# ble_bme690_node.net
KiCad netlist of a schematic drawn in EAGLE
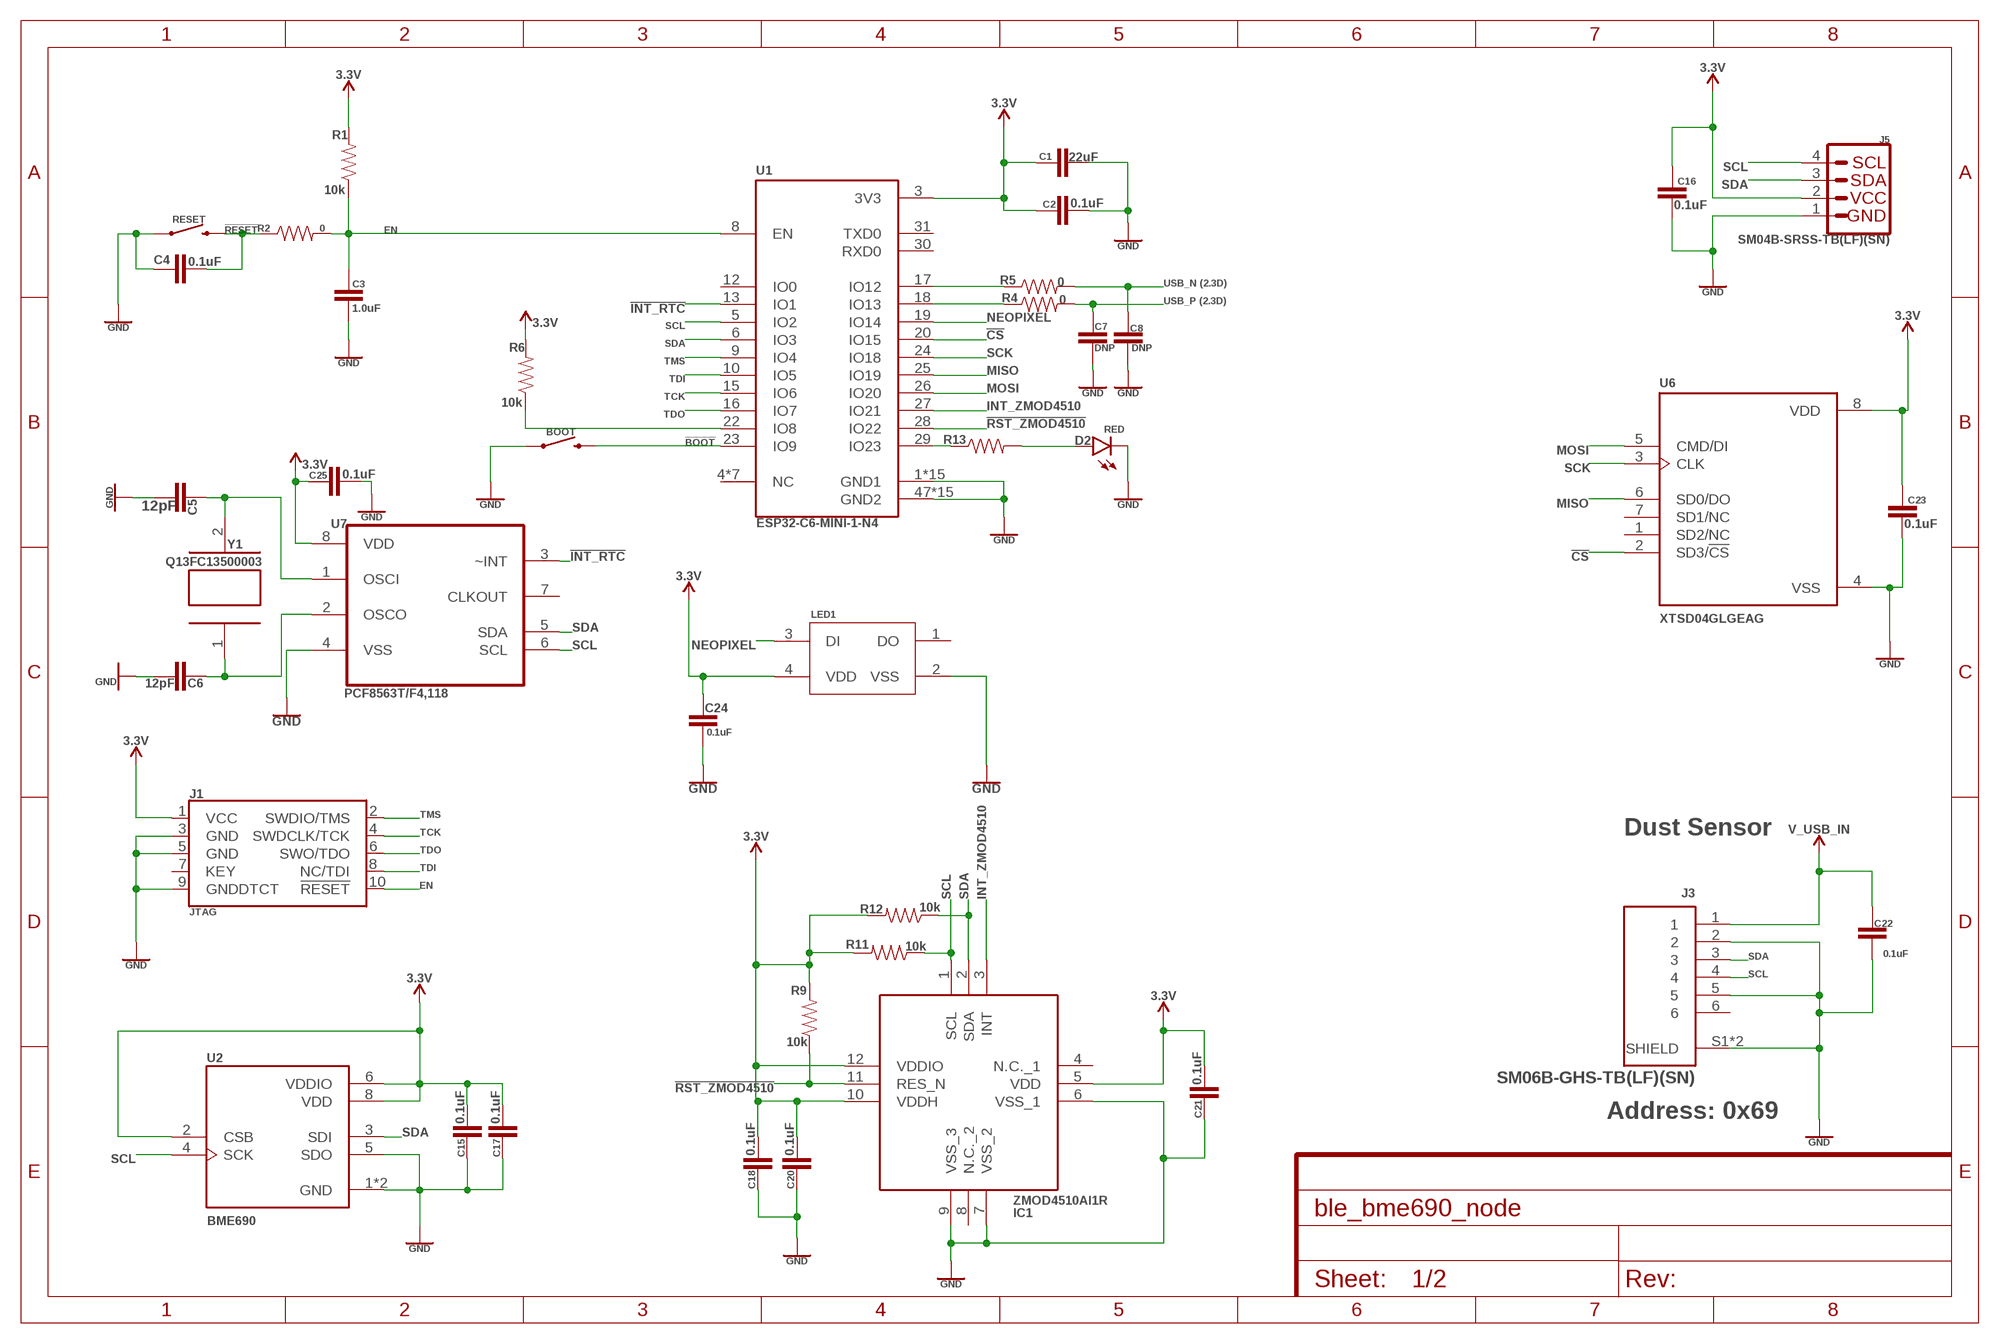
[diagram p0: schematic, sheet 1]
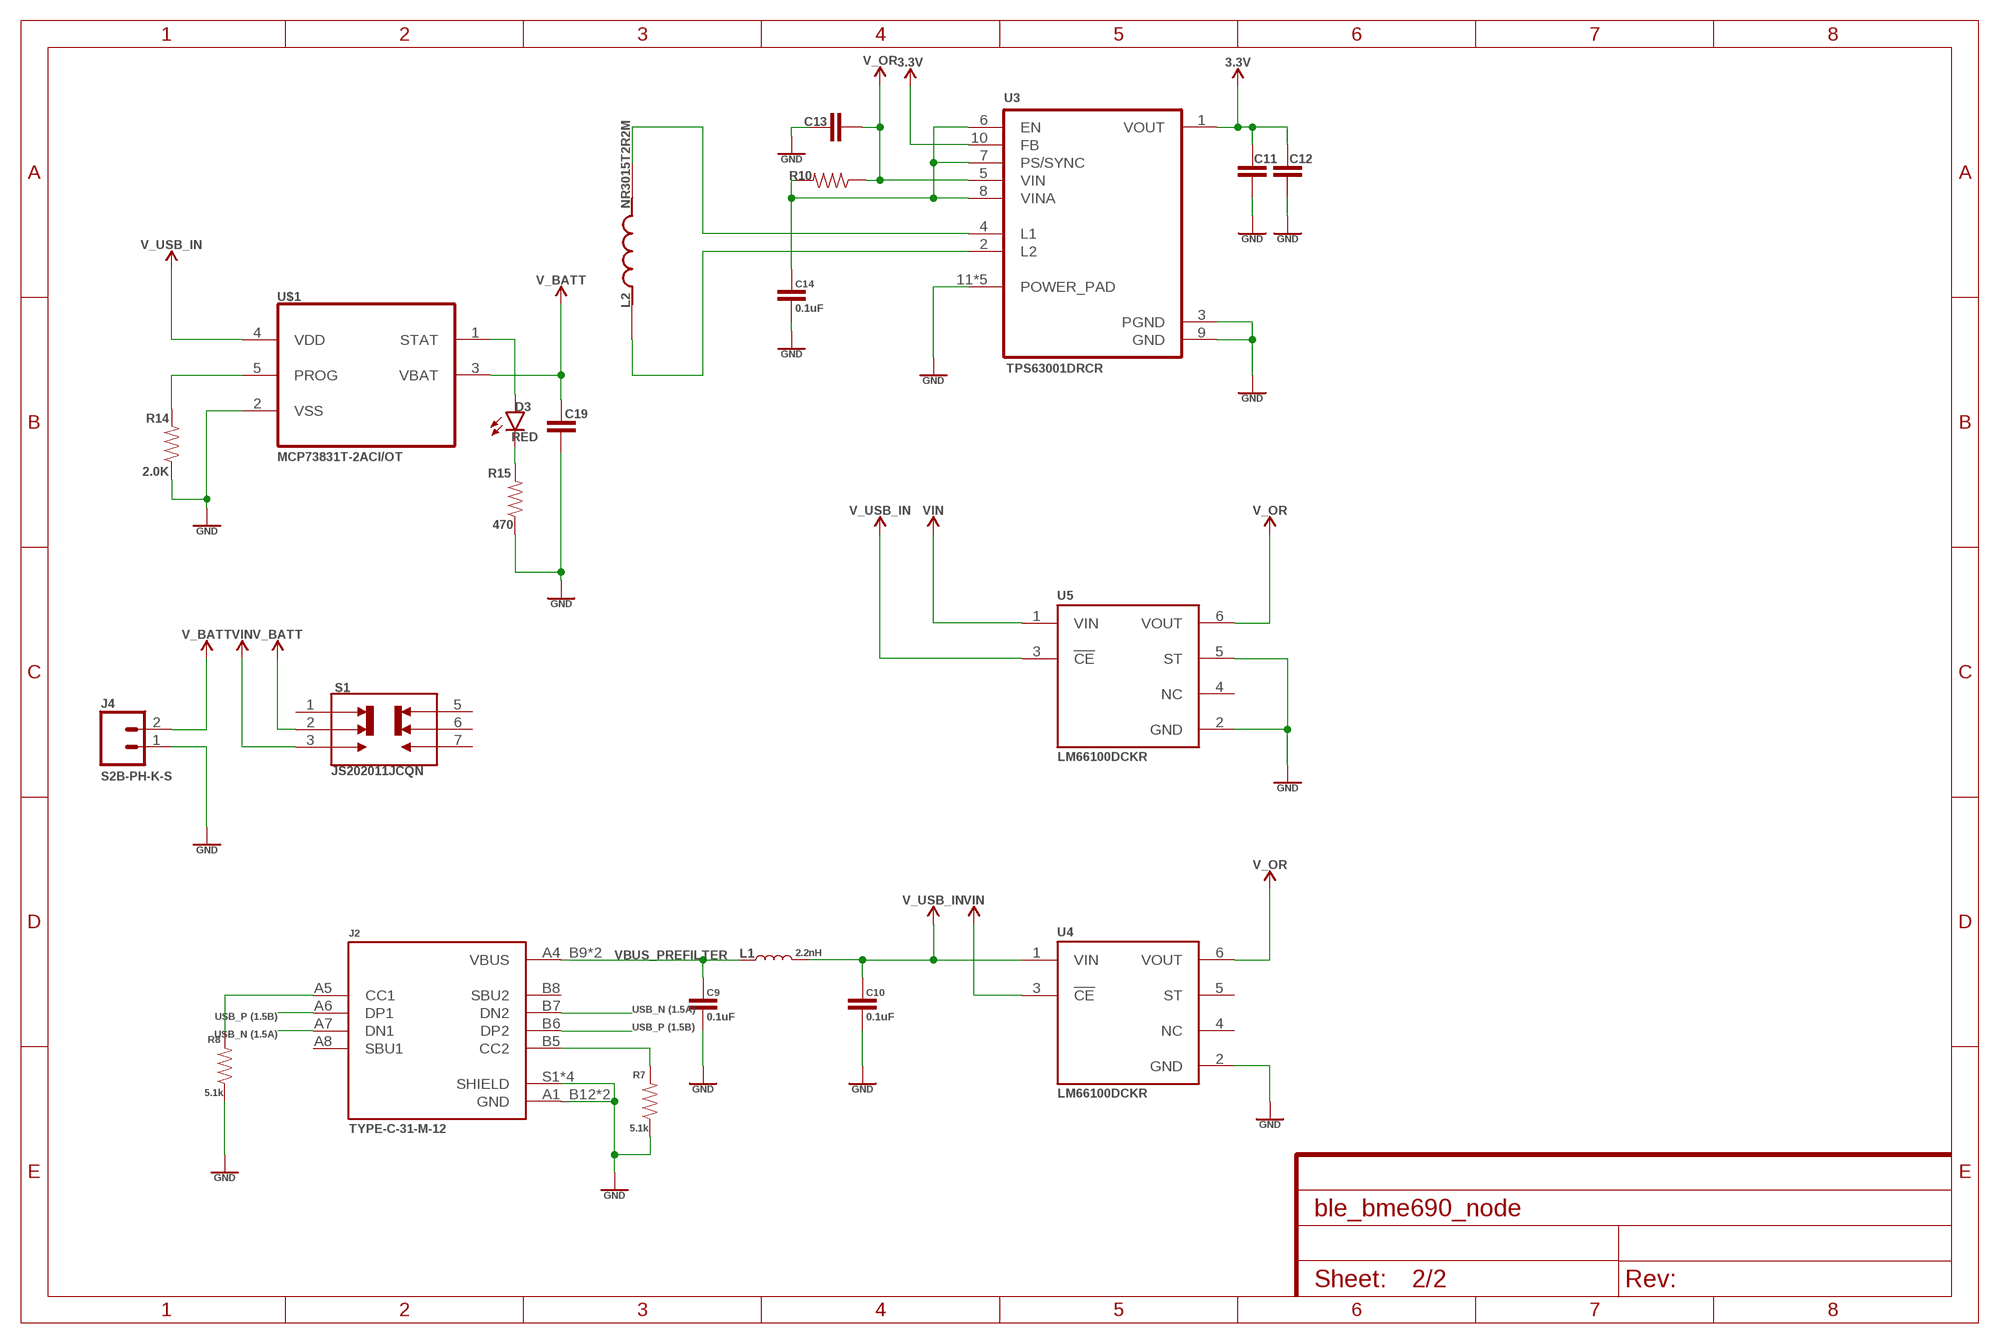
[diagram p1: schematic, sheet 2]

(export (version "E")
  (design (tool "Eeschema 10.0.6"))
  (components
    (comp (ref "BOOT")
      (value "MOMENTARY-SWITCH-SPST-SMD-4.6X2.8MM")
      (footprint "eagle-import:TACTILE_SWITCH_SMD_4.6X2.8MM")
      (libsource (lib "eagle-import") (part "MOMENTARY-SWITCH-SPST-SMD-4.6X2.8MM"))
    )
    (comp (ref "C1")
      (value "22uF")
      (footprint "eagle-import:0603")
      (libsource (lib "eagle-import") (part "22UF-0603-6.3V-20%"))
    )
    (comp (ref "C2")
      (value "0.1uF")
      (footprint "eagle-import:0402")
      (libsource (lib "eagle-import") (part "SparkFun-Capacitors_Sai_0.1UF-0402-6.3V-10%-X7R"))
    )
    (comp (ref "C3")
      (value "1.0uF")
      (footprint "eagle-import:0402")
      (libsource (lib "eagle-import") (part "1.0UF-0402-16V-10%"))
    )
    (comp (ref "C4")
      (value "0.1uF")
      (footprint "eagle-import:0402")
      (libsource (lib "eagle-import") (part "SparkFun-Capacitors_Sai_0.1UF-0402-6.3V-10%-X7R"))
    )
    (comp (ref "C5")
      (value "12pF")
      (footprint "eagle-import:0402")
      (libsource (lib "eagle-import") (part "12PF-0402-50V-5%"))
    )
    (comp (ref "C6")
      (value "12pF")
      (footprint "eagle-import:0402")
      (libsource (lib "eagle-import") (part "12PF-0402-50V-5%"))
    )
    (comp (ref "C7")
      (value "DNP")
      (footprint "eagle-import:0402")
      (libsource (lib "eagle-import") (part "0.1UF-0402-6.3V-10%-X7R"))
    )
    (comp (ref "C8")
      (value "DNP")
      (footprint "eagle-import:0402")
      (libsource (lib "eagle-import") (part "0.1UF-0402-6.3V-10%-X7R"))
    )
    (comp (ref "C15")
      (value "0.1uF")
      (footprint "eagle-import:0402")
      (libsource (lib "eagle-import") (part "SparkFun-Capacitors_Sai_0.1UF-0402-6.3V-10%-X7R"))
    )
    (comp (ref "C16")
      (value "0.1uF")
      (footprint "eagle-import:0402")
      (libsource (lib "eagle-import") (part "SparkFun-Capacitors_Sai_0.1UF-0402-6.3V-10%-X7R"))
    )
    (comp (ref "C17")
      (value "0.1uF")
      (footprint "eagle-import:0402")
      (libsource (lib "eagle-import") (part "SparkFun-Capacitors_Sai_0.1UF-0402-6.3V-10%-X7R"))
    )
    (comp (ref "C18")
      (value "0.1uF")
      (footprint "eagle-import:0402")
      (libsource (lib "eagle-import") (part "SparkFun-Capacitors_Sai_0.1UF-0402-6.3V-10%-X7R"))
    )
    (comp (ref "C20")
      (value "0.1uF")
      (footprint "eagle-import:0402")
      (libsource (lib "eagle-import") (part "SparkFun-Capacitors_Sai_0.1UF-0402-6.3V-10%-X7R"))
    )
    (comp (ref "C21")
      (value "0.1uF")
      (footprint "eagle-import:0402")
      (libsource (lib "eagle-import") (part "SparkFun-Capacitors_Sai_0.1UF-0402-6.3V-10%-X7R"))
    )
    (comp (ref "C22")
      (value "0.1uF")
      (footprint "eagle-import:0402")
      (libsource (lib "eagle-import") (part "0.1UF-0402-16V-10%"))
    )
    (comp (ref "C23")
      (value "0.1uF")
      (footprint "eagle-import:0402")
      (libsource (lib "eagle-import") (part "SparkFun-Capacitors_Sai_0.1UF-0402-6.3V-10%-X7R"))
    )
    (comp (ref "C24")
      (value "0.1uF")
      (footprint "eagle-import:0402")
      (libsource (lib "eagle-import") (part "0.1UF-0402-16V-10%"))
    )
    (comp (ref "C25")
      (value "0.1uF")
      (footprint "eagle-import:0402")
      (libsource (lib "eagle-import") (part "SparkFun-Capacitors_Sai_0.1UF-0402-6.3V-10%-X7R"))
    )
    (comp (ref "D2")
      (value "RED")
      (footprint "eagle-import:LED-0603")
      (libsource (lib "eagle-import") (part "LED-RED0603"))
    )
    (comp (ref "IC1")
      (value "ZMOD4510AI1R")
      (footprint "eagle-import:ZMOD4510AI1R")
      (fields (field (name "MOUSER_PART_NUMBER") "972-ZMOD4510AI1R"))
      (libsource (lib "eagle-import") (part "ZMOD4510AI1R"))
    )
    (comp (ref "J1")
      (value "JTAG")
      (footprint "eagle-import:2X5-SMD-UNSHROUDED")
      (libsource (lib "eagle-import") (part "CORTEX_JTAG_DEBUG_SMD-UNSHROUDED"))
    )
    (comp (ref "J3")
      (value "SM06B-GHS-TB(LF)(SN)")
      (footprint "eagle-import:JST_SM06B-GHS-TB(LF)(SN)")
      (fields (field (name "MF") "JST Sales America Inc."))
      (libsource (lib "eagle-import") (part "SM06B-GHS-TB(LF)(SN)"))
    )
    (comp (ref "J5")
      (value "SM04B-SRSS-TB(LF)(SN)")
      (footprint "eagle-import:1X04_1MM_RA")
      (libsource (lib "eagle-import") (part "QWIIC_CONNECTORJS-1MM"))
    )
    (comp (ref "LED1")
      (value "WS2812B-2020")
      (footprint "eagle-import:WS2812B-2020")
      (fields (field (name "MF") "WorldSemi"))
      (libsource (lib "eagle-import") (part "WS2812B-2020"))
    )
    (comp (ref "R1")
      (value "10k")
      (footprint "eagle-import:0402")
      (libsource (lib "eagle-import") (part "10KOHM-0402-1/16W-1%"))
    )
    (comp (ref "R2")
      (value "0")
      (footprint "eagle-import:0402")
      (libsource (lib "eagle-import") (part "0OHM-0402-1/10W"))
    )
    (comp (ref "R4")
      (value "0")
      (footprint "eagle-import:0402")
      (libsource (lib "eagle-import") (part "0OHM-0402-1/10W"))
    )
    (comp (ref "R5")
      (value "0")
      (footprint "eagle-import:0402")
      (libsource (lib "eagle-import") (part "0OHM-0402-1/10W"))
    )
    (comp (ref "R6")
      (value "10k")
      (footprint "eagle-import:0402")
      (libsource (lib "eagle-import") (part "10KOHM-0402-1/16W-1%"))
    )
    (comp (ref "R9")
      (value "10k")
      (footprint "eagle-import:0402")
      (libsource (lib "eagle-import") (part "10KOHM-0402-1/16W-1%"))
    )
    (comp (ref "R11")
      (value "10k")
      (footprint "eagle-import:0402")
      (libsource (lib "eagle-import") (part "10KOHM-0402-1/16W-1%"))
    )
    (comp (ref "R12")
      (value "10k")
      (footprint "eagle-import:0402")
      (libsource (lib "eagle-import") (part "10KOHM-0402-1/16W-1%"))
    )
    (comp (ref "R13")
      (value "100OHM")
      (footprint "eagle-import:0402")
      (libsource (lib "eagle-import") (part "100OHM"))
    )
    (comp (ref "RESET")
      (value "MOMENTARY-SWITCH-SPST-SMD-4.6X2.8MM")
      (footprint "eagle-import:TACTILE_SWITCH_SMD_4.6X2.8MM")
      (libsource (lib "eagle-import") (part "MOMENTARY-SWITCH-SPST-SMD-4.6X2.8MM"))
    )
    (comp (ref "U1")
      (value "ESP32-C6-MINI-1-N4")
      (footprint "eagle-import:XCVR_ESP32-C6-MINI-1-N4")
      (fields (field (name "MF") "Espressif Systems"))
      (libsource (lib "eagle-import") (part "ESP32-C6-MINI-1-N4"))
    )
    (comp (ref "U2")
      (value "BME690")
      (footprint "eagle-import:IC_BME688")
      (fields (field (name "MF") "Bosch Sensortec") (field (name "MP") "BME688"))
      (libsource (lib "eagle-import") (part "BME690"))
    )
    (comp (ref "U6")
      (value "XTSD04GLGEAG")
      (footprint "eagle-import:SON127P600X800X95-8N")
      (fields (field (name "MF") "XTX"))
      (libsource (lib "eagle-import") (part "XTSD04GLGEAG"))
    )
    (comp (ref "U7")
      (value "PCF8563T/F4,118")
      (footprint "eagle-import:SOIC127P600X175-8N")
      (fields (field (name "MF") "NXP USA"))
      (libsource (lib "eagle-import") (part "PCF8563T/F4,118"))
    )
    (comp (ref "Y1")
      (value "Q13FC13500003")
      (footprint "eagle-import:XTAL_FC-135_32.7680KA-A0")
      (fields (field (name "MF") "EPSON") (field (name "MP") "FC-135 32.7680KA-A0"))
      (libsource (lib "eagle-import") (part "FC-135_32.7680KA-A0"))
    )
    (comp (ref "C9")
      (value "0.1uF")
      (footprint "eagle-import:0402")
      (libsource (lib "eagle-import") (part "SparkFun-Capacitors_Sai_0.1UF-0402-6.3V-10%-X7R"))
    )
    (comp (ref "C10")
      (value "0.1uF")
      (footprint "eagle-import:0402")
      (libsource (lib "eagle-import") (part "SparkFun-Capacitors_Sai_0.1UF-0402-6.3V-10%-X7R"))
    )
    (comp (ref "C11")
      (value "10UF0402")
      (footprint "eagle-import:0402")
      (libsource (lib "eagle-import") (part "10UF0402"))
    )
    (comp (ref "C12")
      (value "10UF0402")
      (footprint "eagle-import:0402")
      (libsource (lib "eagle-import") (part "10UF0402"))
    )
    (comp (ref "C13")
      (value "10UF0402")
      (footprint "eagle-import:0402")
      (libsource (lib "eagle-import") (part "10UF0402"))
    )
    (comp (ref "C14")
      (value "0.1uF")
      (footprint "eagle-import:0402")
      (libsource (lib "eagle-import") (part "SparkFun-Capacitors_Sai_0.1UF-0402-6.3V-10%-X7R"))
    )
    (comp (ref "C19")
      (value "4.7UF0402")
      (footprint "eagle-import:0402")
      (libsource (lib "eagle-import") (part "4.7UF0402"))
    )
    (comp (ref "D3")
      (value "RED")
      (footprint "eagle-import:LED-0603")
      (libsource (lib "eagle-import") (part "LED-RED0603"))
    )
    (comp (ref "J2")
      (value "TYPE-C-31-M-12")
      (footprint "eagle-import:HRO_TYPE-C-31-M-12")
      (fields (field (name "MF") "HRO Electronics Co., Ltd."))
      (libsource (lib "eagle-import") (part "TYPE-C-31-M-12"))
    )
    (comp (ref "J4")
      (value "S2B-PH-K-S")
      (footprint "eagle-import:JST-2-PTH-NS")
      (libsource (lib "eagle-import") (part "CONN_02-JST-2-PTH-NO_SILK"))
    )
    (comp (ref "L1")
      (value "2.2nH")
      (footprint "eagle-import:0603")
      (libsource (lib "eagle-import") (part "3.9NH"))
    )
    (comp (ref "L2")
      (value "NR3015T2R2M")
      (footprint "eagle-import:IND_NR3015T2R2M")
      (fields (field (name "MF") "Taiyo Yuden"))
      (libsource (lib "eagle-import") (part "NR3015T2R2M"))
    )
    (comp (ref "R7")
      (value "5.1k")
      (footprint "eagle-import:0402")
      (libsource (lib "eagle-import") (part "5.1KOHM-0402-1/16W-1%"))
    )
    (comp (ref "R8")
      (value "5.1k")
      (footprint "eagle-import:0402")
      (libsource (lib "eagle-import") (part "5.1KOHM-0402-1/16W-1%"))
    )
    (comp (ref "R10")
      (value "100OHM")
      (footprint "eagle-import:0402")
      (libsource (lib "eagle-import") (part "100OHM"))
    )
    (comp (ref "R14")
      (value "2.0K")
      (footprint "eagle-import:0402")
      (libsource (lib "eagle-import") (part "2.0KOHM-0402-1/16W-1%"))
    )
    (comp (ref "R15")
      (value "470")
      (footprint "eagle-import:0402")
      (libsource (lib "eagle-import") (part "470OHM-0402-1/16W-5%"))
    )
    (comp (ref "S1")
      (value "JS202011JCQN")
      (footprint "eagle-import:SW_JS202011JCQN")
      (fields (field (name "MF") "C&K"))
      (libsource (lib "eagle-import") (part "JS202011JCQN"))
    )
    (comp (ref "U$1")
      (value "MCP73831T-2ACI/OT")
      (footprint "eagle-import:SOT95P280X145-5N")
      (fields (field (name "MF") "Microchip"))
      (libsource (lib "eagle-import") (part "MCP73831T-2ACI/OT"))
    )
    (comp (ref "U3")
      (value "TPS63001DRCR")
      (footprint "eagle-import:VREG_V62_16624-01YE")
      (fields (field (name "MF") "Texas Instruments"))
      (libsource (lib "eagle-import") (part "TPS63001DRCR"))
    )
    (comp (ref "U4")
      (value "LM66100DCKR")
      (footprint "eagle-import:SOT65P210X110-6N")
      (fields (field (name "MF") "Texas Instruments"))
      (libsource (lib "eagle-import") (part "LM66100DCKR"))
    )
    (comp (ref "U5")
      (value "LM66100DCKR")
      (footprint "eagle-import:SOT65P210X110-6N")
      (fields (field (name "MF") "Texas Instruments"))
      (libsource (lib "eagle-import") (part "LM66100DCKR"))
    )
  )
  (nets
    (net (code "1") (name "3.3V") (class "Default")
      (node (ref "C1") (pin "1") (pinfunction "1_1") (pintype "passive"))
      (node (ref "C11") (pin "1") (pinfunction "1_1") (pintype "passive"))
      (node (ref "C12") (pin "1") (pinfunction "1_1") (pintype "passive"))
      (node (ref "C15") (pin "2") (pinfunction "2_2") (pintype "passive"))
      (node (ref "C16") (pin "2") (pinfunction "2_2") (pintype "passive"))
      (node (ref "C17") (pin "2") (pinfunction "2_2") (pintype "passive"))
      (node (ref "C18") (pin "2") (pinfunction "2_2") (pintype "passive"))
      (node (ref "C2") (pin "1") (pinfunction "1_1") (pintype "passive"))
      (node (ref "C20") (pin "2") (pinfunction "2_2") (pintype "passive"))
      (node (ref "C21") (pin "2") (pinfunction "2_2") (pintype "passive"))
      (node (ref "C23") (pin "2") (pinfunction "2_2") (pintype "passive"))
      (node (ref "C24") (pin "1") (pinfunction "1_1") (pintype "passive"))
      (node (ref "C25") (pin "1") (pinfunction "1_1") (pintype "passive"))
      (node (ref "IC1") (pin "10") (pinfunction "VDDH_10") (pintype "bidirectional"))
      (node (ref "IC1") (pin "12") (pinfunction "VDDIO_12") (pintype "bidirectional"))
      (node (ref "IC1") (pin "5") (pinfunction "VDD_5") (pintype "bidirectional"))
      (node (ref "J1") (pin "1") (pinfunction "VCC_1") (pintype "bidirectional"))
      (node (ref "J5") (pin "2") (pinfunction "2_2") (pintype "power_in"))
      (node (ref "LED1") (pin "4") (pinfunction "VDD_4") (pintype "bidirectional"))
      (node (ref "R1") (pin "2") (pinfunction "2_2") (pintype "passive"))
      (node (ref "R11") (pin "2") (pinfunction "2_2") (pintype "passive"))
      (node (ref "R12") (pin "2") (pinfunction "2_2") (pintype "passive"))
      (node (ref "R6") (pin "2") (pinfunction "2_2") (pintype "passive"))
      (node (ref "R9") (pin "2") (pinfunction "2_2") (pintype "passive"))
      (node (ref "U1") (pin "3") (pinfunction "3V3_3") (pintype "power_in"))
      (node (ref "U2") (pin "2") (pinfunction "CSB_2") (pintype "input"))
      (node (ref "U2") (pin "6") (pinfunction "VDDIO_6") (pintype "power_in"))
      (node (ref "U2") (pin "8") (pinfunction "VDD_8") (pintype "power_in"))
      (node (ref "U3") (pin "1") (pinfunction "VOUT_1") (pintype "output"))
      (node (ref "U3") (pin "10") (pinfunction "FB_10") (pintype "input"))
      (node (ref "U6") (pin "8") (pinfunction "VDD_8") (pintype "power_in"))
      (node (ref "U7") (pin "8") (pinfunction "VDD_8") (pintype "power_in"))
    )
    (net (code "2") (name "EN") (class "Default")
      (node (ref "C3") (pin "2") (pinfunction "2_2") (pintype "passive"))
      (node (ref "J1") (pin "10") (pinfunction "~{RESET}_10") (pintype "bidirectional"))
      (node (ref "R1") (pin "1") (pinfunction "1_1") (pintype "passive"))
      (node (ref "R2") (pin "2") (pinfunction "2_2") (pintype "passive"))
      (node (ref "U1") (pin "8") (pinfunction "EN_8") (pintype "input"))
    )
    (net (code "3") (name "GND") (class "Default")
      (node (ref "BOOT") (pin "1") (pinfunction "1_1") (pintype "passive"))
      (node (ref "BOOT") (pin "2") (pinfunction "1_2") (pintype "passive"))
      (node (ref "C1") (pin "2") (pinfunction "2_2") (pintype "passive"))
      (node (ref "C10") (pin "1") (pinfunction "1_1") (pintype "passive"))
      (node (ref "C11") (pin "2") (pinfunction "2_2") (pintype "passive"))
      (node (ref "C12") (pin "2") (pinfunction "2_2") (pintype "passive"))
      (node (ref "C13") (pin "1") (pinfunction "1_1") (pintype "passive"))
      (node (ref "C14") (pin "1") (pinfunction "1_1") (pintype "passive"))
      (node (ref "C15") (pin "1") (pinfunction "1_1") (pintype "passive"))
      (node (ref "C16") (pin "1") (pinfunction "1_1") (pintype "passive"))
      (node (ref "C17") (pin "1") (pinfunction "1_1") (pintype "passive"))
      (node (ref "C18") (pin "1") (pinfunction "1_1") (pintype "passive"))
      (node (ref "C19") (pin "2") (pinfunction "2_2") (pintype "passive"))
      (node (ref "C2") (pin "2") (pinfunction "2_2") (pintype "passive"))
      (node (ref "C20") (pin "1") (pinfunction "1_1") (pintype "passive"))
      (node (ref "C21") (pin "1") (pinfunction "1_1") (pintype "passive"))
      (node (ref "C22") (pin "2") (pinfunction "2_2") (pintype "passive"))
      (node (ref "C23") (pin "1") (pinfunction "1_1") (pintype "passive"))
      (node (ref "C24") (pin "2") (pinfunction "2_2") (pintype "passive"))
      (node (ref "C25") (pin "2") (pinfunction "2_2") (pintype "passive"))
      (node (ref "C3") (pin "1") (pinfunction "1_1") (pintype "passive"))
      (node (ref "C4") (pin "1") (pinfunction "1_1") (pintype "passive"))
      (node (ref "C5") (pin "2") (pinfunction "2_2") (pintype "passive"))
      (node (ref "C6") (pin "2") (pinfunction "2_2") (pintype "passive"))
      (node (ref "C7") (pin "2") (pinfunction "2_2") (pintype "passive"))
      (node (ref "C8") (pin "2") (pinfunction "2_2") (pintype "passive"))
      (node (ref "C9") (pin "1") (pinfunction "1_1") (pintype "passive"))
      (node (ref "D2") (pin "C") (pinfunction "C_C") (pintype "passive"))
      (node (ref "IC1") (pin "6") (pinfunction "VSS_1_6") (pintype "bidirectional"))
      (node (ref "IC1") (pin "7") (pinfunction "VSS_2_7") (pintype "bidirectional"))
      (node (ref "IC1") (pin "9") (pinfunction "VSS_3_9") (pintype "bidirectional"))
      (node (ref "J1") (pin "3") (pinfunction "GND_3") (pintype "bidirectional"))
      (node (ref "J1") (pin "5") (pinfunction "GND_5") (pintype "bidirectional"))
      (node (ref "J1") (pin "9") (pinfunction "GNDDTCT_9") (pintype "bidirectional"))
      (node (ref "J2") (pin "A1_B12") (pinfunction "GND_A1_B12") (pintype "power_in"))
      (node (ref "J2") (pin "B1_A12") (pinfunction "GND_B1_A12") (pintype "power_in"))
      (node (ref "J2") (pin "S1") (pinfunction "SHIELD_S1") (pintype "passive"))
      (node (ref "J2") (pin "S2") (pinfunction "SHIELD_S2") (pintype "passive"))
      (node (ref "J2") (pin "S3") (pinfunction "SHIELD_S3") (pintype "passive"))
      (node (ref "J2") (pin "S4") (pinfunction "SHIELD_S4") (pintype "passive"))
      (node (ref "J3") (pin "2") (pinfunction "2_2") (pintype "passive"))
      (node (ref "J3") (pin "5") (pinfunction "5_5") (pintype "passive"))
      (node (ref "J3") (pin "S1") (pinfunction "SHIELD_S1") (pintype "passive"))
      (node (ref "J3") (pin "S2") (pinfunction "SHIELD_S2") (pintype "passive"))
      (node (ref "J4") (pin "1") (pinfunction "1_1") (pintype "passive"))
      (node (ref "J5") (pin "1") (pinfunction "1_1") (pintype "power_in"))
      (node (ref "LED1") (pin "2") (pinfunction "VSS_2") (pintype "bidirectional"))
      (node (ref "R14") (pin "1") (pinfunction "1_1") (pintype "passive"))
      (node (ref "R15") (pin "1") (pinfunction "1_1") (pintype "passive"))
      (node (ref "R7") (pin "1") (pinfunction "1_1") (pintype "passive"))
      (node (ref "R8") (pin "1") (pinfunction "1_1") (pintype "passive"))
      (node (ref "RESET") (pin "1") (pinfunction "1_1") (pintype "passive"))
      (node (ref "RESET") (pin "2") (pinfunction "1_2") (pintype "passive"))
      (node (ref "U$1") (pin "2") (pinfunction "VSS_2") (pintype "power_in"))
      (node (ref "U1") (pin "1") (pinfunction "GND1_1") (pintype "power_in"))
      (node (ref "U1") (pin "11") (pinfunction "GND1_11") (pintype "power_in"))
      (node (ref "U1") (pin "14") (pinfunction "GND1_14") (pintype "power_in"))
      (node (ref "U1") (pin "2") (pinfunction "GND1_2") (pintype "power_in"))
      (node (ref "U1") (pin "36") (pinfunction "GND1_36") (pintype "power_in"))
      (node (ref "U1") (pin "37") (pinfunction "GND1_37") (pintype "power_in"))
      (node (ref "U1") (pin "38") (pinfunction "GND1_38") (pintype "power_in"))
      (node (ref "U1") (pin "39") (pinfunction "GND1_39") (pintype "power_in"))
      (node (ref "U1") (pin "40") (pinfunction "GND1_40") (pintype "power_in"))
      (node (ref "U1") (pin "41") (pinfunction "GND1_41") (pintype "power_in"))
      (node (ref "U1") (pin "42") (pinfunction "GND1_42") (pintype "power_in"))
      (node (ref "U1") (pin "43") (pinfunction "GND1_43") (pintype "power_in"))
      (node (ref "U1") (pin "44") (pinfunction "GND1_44") (pintype "power_in"))
      (node (ref "U1") (pin "45") (pinfunction "GND1_45") (pintype "power_in"))
      (node (ref "U1") (pin "46") (pinfunction "GND1_46") (pintype "power_in"))
      (node (ref "U1") (pin "47") (pinfunction "GND2_47") (pintype "power_in"))
      (node (ref "U1") (pin "48") (pinfunction "GND2_48") (pintype "power_in"))
      (node (ref "U1") (pin "49_1") (pinfunction "GND2_49_1") (pintype "power_in"))
      (node (ref "U1") (pin "49_2") (pinfunction "GND2_49_2") (pintype "power_in"))
      (node (ref "U1") (pin "49_3") (pinfunction "GND2_49_3") (pintype "power_in"))
      (node (ref "U1") (pin "49_4") (pinfunction "GND2_49_4") (pintype "power_in"))
      (node (ref "U1") (pin "49_5") (pinfunction "GND2_49_5") (pintype "power_in"))
      (node (ref "U1") (pin "49_6") (pinfunction "GND2_49_6") (pintype "power_in"))
      (node (ref "U1") (pin "49_7") (pinfunction "GND2_49_7") (pintype "power_in"))
      (node (ref "U1") (pin "49_8") (pinfunction "GND2_49_8") (pintype "power_in"))
      (node (ref "U1") (pin "49_9") (pinfunction "GND2_49_9") (pintype "power_in"))
      (node (ref "U1") (pin "50") (pinfunction "GND2_50") (pintype "power_in"))
      (node (ref "U1") (pin "51") (pinfunction "GND2_51") (pintype "power_in"))
      (node (ref "U1") (pin "52") (pinfunction "GND2_52") (pintype "power_in"))
      (node (ref "U1") (pin "53") (pinfunction "GND2_53") (pintype "power_in"))
      (node (ref "U2") (pin "1") (pinfunction "GND_1") (pintype "power_in"))
      (node (ref "U2") (pin "5") (pinfunction "SDO_5") (pintype "bidirectional"))
      (node (ref "U2") (pin "7") (pinfunction "GND_7") (pintype "power_in"))
      (node (ref "U3") (pin "11") (pinfunction "POWER_PAD_11") (pintype "bidirectional"))
      (node (ref "U3") (pin "12") (pinfunction "POWER_PAD_12") (pintype "bidirectional"))
      (node (ref "U3") (pin "13") (pinfunction "POWER_PAD_13") (pintype "bidirectional"))
      (node (ref "U3") (pin "14") (pinfunction "POWER_PAD_14") (pintype "bidirectional"))
      (node (ref "U3") (pin "15") (pinfunction "POWER_PAD_15") (pintype "bidirectional"))
      (node (ref "U3") (pin "3") (pinfunction "PGND_3") (pintype "power_in"))
      (node (ref "U3") (pin "9") (pinfunction "GND_9") (pintype "power_in"))
      (node (ref "U4") (pin "2") (pinfunction "GND_2") (pintype "power_in"))
      (node (ref "U5") (pin "2") (pinfunction "GND_2") (pintype "power_in"))
      (node (ref "U5") (pin "5") (pinfunction "ST_5") (pintype "output"))
      (node (ref "U6") (pin "4") (pinfunction "VSS_4") (pintype "power_in"))
      (node (ref "U7") (pin "4") (pinfunction "VSS_4") (pintype "power_in"))
    )
    (net (code "4") (name "INT_ZMOD4510") (class "Default")
      (node (ref "IC1") (pin "3") (pinfunction "INT_3") (pintype "bidirectional"))
      (node (ref "U1") (pin "27") (pinfunction "IO21_27") (pintype "bidirectional"))
    )
    (net (code "5") (name "MISO") (class "Default")
      (node (ref "U1") (pin "25") (pinfunction "IO19_25") (pintype "bidirectional"))
      (node (ref "U6") (pin "6") (pinfunction "SD0/DO_6") (pintype "bidirectional"))
    )
    (net (code "6") (name "MOSI") (class "Default")
      (node (ref "U1") (pin "26") (pinfunction "IO20_26") (pintype "bidirectional"))
      (node (ref "U6") (pin "5") (pinfunction "CMD/DI_5") (pintype "input"))
    )
    (net (code "7") (name "NEOPIXEL") (class "Default")
      (node (ref "LED1") (pin "3") (pinfunction "DI_3") (pintype "bidirectional"))
      (node (ref "U1") (pin "19") (pinfunction "IO14_19") (pintype "bidirectional"))
    )
    (net (code "8") (name "Net-(D2-PadA)") (class "Default")
      (node (ref "D2") (pin "A") (pinfunction "A_A") (pintype "passive"))
      (node (ref "R13") (pin "2") (pinfunction "2_2") (pintype "passive"))
    )
    (net (code "9") (name "Net-(D3-PadC)") (class "Default")
      (node (ref "D3") (pin "C") (pinfunction "C_C") (pintype "passive"))
      (node (ref "R15") (pin "2") (pinfunction "2_2") (pintype "passive"))
    )
    (net (code "10") (name "Net-(J2-CC1)") (class "Default")
      (node (ref "J2") (pin "A5") (pinfunction "CC1_A5") (pintype "bidirectional"))
      (node (ref "R8") (pin "2") (pinfunction "2_2") (pintype "passive"))
    )
    (net (code "11") (name "Net-(J2-CC2)") (class "Default")
      (node (ref "J2") (pin "B5") (pinfunction "CC2_B5") (pintype "bidirectional"))
      (node (ref "R7") (pin "2") (pinfunction "2_2") (pintype "passive"))
    )
    (net (code "12") (name "Net-(U$1-PROG)") (class "Default")
      (node (ref "R14") (pin "2") (pinfunction "2_2") (pintype "passive"))
      (node (ref "U$1") (pin "5") (pinfunction "PROG_5") (pintype "input"))
    )
    (net (code "13") (name "Net-(U$1-STAT)") (class "Default")
      (node (ref "D3") (pin "A") (pinfunction "A_A") (pintype "passive"))
      (node (ref "U$1") (pin "1") (pinfunction "STAT_1") (pintype "output"))
    )
    (net (code "14") (name "Net-(U1-IO8)") (class "Default")
      (node (ref "R6") (pin "1") (pinfunction "1_1") (pintype "passive"))
      (node (ref "U1") (pin "22") (pinfunction "IO8_22") (pintype "bidirectional"))
    )
    (net (code "15") (name "Net-(U1-IO12)") (class "Default")
      (node (ref "R5") (pin "1") (pinfunction "1_1") (pintype "passive"))
      (node (ref "U1") (pin "17") (pinfunction "IO12_17") (pintype "bidirectional"))
    )
    (net (code "16") (name "Net-(U1-IO13)") (class "Default")
      (node (ref "R4") (pin "1") (pinfunction "1_1") (pintype "passive"))
      (node (ref "U1") (pin "18") (pinfunction "IO13_18") (pintype "bidirectional"))
    )
    (net (code "17") (name "Net-(U1-IO23)") (class "Default")
      (node (ref "R13") (pin "1") (pinfunction "1_1") (pintype "passive"))
      (node (ref "U1") (pin "29") (pinfunction "IO23_29") (pintype "bidirectional"))
    )
    (net (code "18") (name "Net-(U3-EN)") (class "Default")
      (node (ref "C14") (pin "2") (pinfunction "2_2") (pintype "passive"))
      (node (ref "R10") (pin "2") (pinfunction "2_2") (pintype "passive"))
      (node (ref "U3") (pin "6") (pinfunction "EN_6") (pintype "input"))
      (node (ref "U3") (pin "7") (pinfunction "PS/SYNC_7") (pintype "input"))
      (node (ref "U3") (pin "8") (pinfunction "VINA_8") (pintype "input"))
    )
    (net (code "19") (name "Net-(U3-L1)") (class "Default")
      (node (ref "L2") (pin "2") (pinfunction "2_2") (pintype "passive"))
      (node (ref "U3") (pin "4") (pinfunction "L1_4") (pintype "bidirectional"))
    )
    (net (code "20") (name "Net-(U3-L2)") (class "Default")
      (node (ref "L2") (pin "1") (pinfunction "1_1") (pintype "passive"))
      (node (ref "U3") (pin "2") (pinfunction "L2_2") (pintype "bidirectional"))
    )
    (net (code "21") (name "Net-(U7-OSCI)") (class "Default")
      (node (ref "C5") (pin "1") (pinfunction "1_1") (pintype "passive"))
      (node (ref "U7") (pin "1") (pinfunction "OSCI_1") (pintype "input"))
      (node (ref "Y1") (pin "2") (pinfunction "2_2") (pintype "passive"))
    )
    (net (code "22") (name "Net-(U7-OSCO)") (class "Default")
      (node (ref "C6") (pin "1") (pinfunction "1_1") (pintype "passive"))
      (node (ref "U7") (pin "2") (pinfunction "OSCO_2") (pintype "output"))
      (node (ref "Y1") (pin "1") (pinfunction "1_1") (pintype "passive"))
    )
    (net (code "23") (name "SCK") (class "Default")
      (node (ref "U1") (pin "24") (pinfunction "IO18_24") (pintype "bidirectional"))
      (node (ref "U6") (pin "3") (pinfunction "CLK_3") (pintype "input"))
    )
    (net (code "24") (name "SCL") (class "Default")
      (node (ref "IC1") (pin "1") (pinfunction "SCL_1") (pintype "bidirectional"))
      (node (ref "J3") (pin "4") (pinfunction "4_4") (pintype "passive"))
      (node (ref "J5") (pin "4") (pinfunction "4_4") (pintype "passive"))
      (node (ref "R11") (pin "1") (pinfunction "1_1") (pintype "passive"))
      (node (ref "U1") (pin "5") (pinfunction "IO2_5") (pintype "bidirectional"))
      (node (ref "U2") (pin "4") (pinfunction "SCK_4") (pintype "input"))
      (node (ref "U7") (pin "6") (pinfunction "SCL_6") (pintype "input"))
    )
    (net (code "25") (name "SDA") (class "Default")
      (node (ref "IC1") (pin "2") (pinfunction "SDA_2") (pintype "bidirectional"))
      (node (ref "J3") (pin "3") (pinfunction "3_3") (pintype "passive"))
      (node (ref "J5") (pin "3") (pinfunction "3_3") (pintype "passive"))
      (node (ref "R12") (pin "1") (pinfunction "1_1") (pintype "passive"))
      (node (ref "U1") (pin "6") (pinfunction "IO3_6") (pintype "bidirectional"))
      (node (ref "U2") (pin "3") (pinfunction "SDI_3") (pintype "bidirectional"))
      (node (ref "U7") (pin "5") (pinfunction "SDA_5") (pintype "bidirectional"))
    )
    (net (code "26") (name "TCK") (class "Default")
      (node (ref "J1") (pin "4") (pinfunction "SWDCLK/TCK_4") (pintype "bidirectional"))
      (node (ref "U1") (pin "15") (pinfunction "IO6_15") (pintype "bidirectional"))
    )
    (net (code "27") (name "TDI") (class "Default")
      (node (ref "J1") (pin "8") (pinfunction "NC/TDI_8") (pintype "bidirectional"))
      (node (ref "U1") (pin "10") (pinfunction "IO5_10") (pintype "bidirectional"))
    )
    (net (code "28") (name "TDO") (class "Default")
      (node (ref "J1") (pin "6") (pinfunction "SWO/TDO_6") (pintype "bidirectional"))
      (node (ref "U1") (pin "16") (pinfunction "IO7_16") (pintype "bidirectional"))
    )
    (net (code "29") (name "TMS") (class "Default")
      (node (ref "J1") (pin "2") (pinfunction "SWDIO/TMS_2") (pintype "bidirectional"))
      (node (ref "U1") (pin "9") (pinfunction "IO4_9") (pintype "bidirectional"))
    )
    (net (code "30") (name "USB_N") (class "Default")
      (node (ref "C8") (pin "1") (pinfunction "1_1") (pintype "passive"))
      (node (ref "J2") (pin "A7") (pinfunction "DN1_A7") (pintype "bidirectional"))
      (node (ref "J2") (pin "B7") (pinfunction "DN2_B7") (pintype "bidirectional"))
      (node (ref "R5") (pin "2") (pinfunction "2_2") (pintype "passive"))
    )
    (net (code "31") (name "USB_P") (class "Default")
      (node (ref "C7") (pin "1") (pinfunction "1_1") (pintype "passive"))
      (node (ref "J2") (pin "A6") (pinfunction "DP1_A6") (pintype "bidirectional"))
      (node (ref "J2") (pin "B6") (pinfunction "DP2_B6") (pintype "bidirectional"))
      (node (ref "R4") (pin "2") (pinfunction "2_2") (pintype "passive"))
    )
    (net (code "32") (name "VBUS_PREFILTER") (class "Default")
      (node (ref "C9") (pin "2") (pinfunction "2_2") (pintype "passive"))
      (node (ref "J2") (pin "A4_B9") (pinfunction "VBUS_A4_B9") (pintype "power_in"))
      (node (ref "J2") (pin "B4_A9") (pinfunction "VBUS_B4_A9") (pintype "power_in"))
      (node (ref "L1") (pin "1") (pinfunction "1_1") (pintype "passive"))
    )
    (net (code "33") (name "VIN") (class "Default")
      (node (ref "S1") (pin "3") (pinfunction "3_3") (pintype "passive"))
      (node (ref "U4") (pin "3") (pinfunction "~{CE}_3") (pintype "input"))
      (node (ref "U5") (pin "1") (pinfunction "VIN_1") (pintype "input"))
    )
    (net (code "34") (name "VREF1") (class "Default")
      (node (ref "C13") (pin "2") (pinfunction "2_2") (pintype "passive"))
      (node (ref "R10") (pin "1") (pinfunction "1_1") (pintype "passive"))
      (node (ref "U3") (pin "5") (pinfunction "VIN_5") (pintype "input"))
      (node (ref "U4") (pin "6") (pinfunction "VOUT_6") (pintype "output"))
      (node (ref "U5") (pin "6") (pinfunction "VOUT_6") (pintype "output"))
    )
    (net (code "35") (name "V_BATT") (class "Default")
      (node (ref "C19") (pin "1") (pinfunction "1_1") (pintype "passive"))
      (node (ref "J4") (pin "2") (pinfunction "2_2") (pintype "passive"))
      (node (ref "S1") (pin "2") (pinfunction "2_2") (pintype "passive"))
      (node (ref "U$1") (pin "3") (pinfunction "VBAT_3") (pintype "output"))
    )
    (net (code "36") (name "V_USB_2") (class "Default")
      (node (ref "C10") (pin "2") (pinfunction "2_2") (pintype "passive"))
      (node (ref "C22") (pin "1") (pinfunction "1_1") (pintype "passive"))
      (node (ref "J3") (pin "1") (pinfunction "1_1") (pintype "passive"))
      (node (ref "L1") (pin "2") (pinfunction "2_2") (pintype "passive"))
      (node (ref "U$1") (pin "4") (pinfunction "VDD_4") (pintype "power_in"))
      (node (ref "U4") (pin "1") (pinfunction "VIN_1") (pintype "input"))
      (node (ref "U5") (pin "3") (pinfunction "~{CE}_3") (pintype "input"))
    )
    (net (code "37") (name "unconnected-(IC1-N.C._1-Pad4)") (class "Default")
      (node (ref "IC1") (pin "4") (pinfunction "N.C._1_4") (pintype "bidirectional"))
    )
    (net (code "38") (name "unconnected-(IC1-N.C._2-Pad8)") (class "Default")
      (node (ref "IC1") (pin "8") (pinfunction "N.C._2_8") (pintype "bidirectional"))
    )
    (net (code "39") (name "unconnected-(J1-KEY-Pad7)") (class "Default")
      (node (ref "J1") (pin "7") (pinfunction "KEY_7") (pintype "bidirectional"))
    )
    (net (code "40") (name "unconnected-(J2-SBU1-PadA8)") (class "Default")
      (node (ref "J2") (pin "A8") (pinfunction "SBU1_A8") (pintype "bidirectional"))
    )
    (net (code "41") (name "unconnected-(J2-SBU2-PadB8)") (class "Default")
      (node (ref "J2") (pin "B8") (pinfunction "SBU2_B8") (pintype "bidirectional"))
    )
    (net (code "42") (name "unconnected-(J3-Pad6)") (class "Default")
      (node (ref "J3") (pin "6") (pinfunction "6_6") (pintype "passive"))
    )
    (net (code "43") (name "unconnected-(LED1-DO-Pad1)") (class "Default")
      (node (ref "LED1") (pin "1") (pinfunction "DO_1") (pintype "bidirectional"))
    )
    (net (code "44") (name "unconnected-(S1-Pad1)") (class "Default")
      (node (ref "S1") (pin "1") (pinfunction "1_1") (pintype "passive"))
    )
    (net (code "45") (name "unconnected-(S1-Pad5)") (class "Default")
      (node (ref "S1") (pin "5") (pinfunction "5_5") (pintype "passive"))
    )
    (net (code "46") (name "unconnected-(S1-Pad6)") (class "Default")
      (node (ref "S1") (pin "6") (pinfunction "6_6") (pintype "passive"))
    )
    (net (code "47") (name "unconnected-(S1-Pad7)") (class "Default")
      (node (ref "S1") (pin "7") (pinfunction "7_7") (pintype "passive"))
    )
    (net (code "48") (name "unconnected-(U1-IO0-Pad12)") (class "Default")
      (node (ref "U1") (pin "12") (pinfunction "IO0_12") (pintype "bidirectional"))
    )
    (net (code "49") (name "unconnected-(U1-NC-Pad4)") (class "Default")
      (node (ref "U1") (pin "4") (pinfunction "NC_4") (pintype "no_connect"))
    )
    (net (code "50") (name "unconnected-(U1-NC-Pad7)") (class "Default")
      (node (ref "U1") (pin "7") (pinfunction "NC_7") (pintype "no_connect"))
    )
    (net (code "51") (name "unconnected-(U1-NC-Pad21)") (class "Default")
      (node (ref "U1") (pin "21") (pinfunction "NC_21") (pintype "no_connect"))
    )
    (net (code "52") (name "unconnected-(U1-NC-Pad32)") (class "Default")
      (node (ref "U1") (pin "32") (pinfunction "NC_32") (pintype "no_connect"))
    )
    (net (code "53") (name "unconnected-(U1-NC-Pad33)") (class "Default")
      (node (ref "U1") (pin "33") (pinfunction "NC_33") (pintype "no_connect"))
    )
    (net (code "54") (name "unconnected-(U1-NC-Pad34)") (class "Default")
      (node (ref "U1") (pin "34") (pinfunction "NC_34") (pintype "no_connect"))
    )
    (net (code "55") (name "unconnected-(U1-NC-Pad35)") (class "Default")
      (node (ref "U1") (pin "35") (pinfunction "NC_35") (pintype "no_connect"))
    )
    (net (code "56") (name "unconnected-(U1-RXD0-Pad30)") (class "Default")
      (node (ref "U1") (pin "30") (pinfunction "RXD0_30") (pintype "bidirectional"))
    )
    (net (code "57") (name "unconnected-(U1-TXD0-Pad31)") (class "Default")
      (node (ref "U1") (pin "31") (pinfunction "TXD0_31") (pintype "bidirectional"))
    )
    (net (code "58") (name "unconnected-(U4-NC-Pad4)") (class "Default")
      (node (ref "U4") (pin "4") (pinfunction "NC_4") (pintype "no_connect"))
    )
    (net (code "59") (name "unconnected-(U4-ST-Pad5)") (class "Default")
      (node (ref "U4") (pin "5") (pinfunction "ST_5") (pintype "output"))
    )
    (net (code "60") (name "unconnected-(U5-NC-Pad4)") (class "Default")
      (node (ref "U5") (pin "4") (pinfunction "NC_4") (pintype "no_connect"))
    )
    (net (code "61") (name "unconnected-(U6-SD1{slash}NC-Pad7)") (class "Default")
      (node (ref "U6") (pin "7") (pinfunction "SD1/NC_7") (pintype "bidirectional"))
    )
    (net (code "62") (name "unconnected-(U6-SD2{slash}NC-Pad1)") (class "Default")
      (node (ref "U6") (pin "1") (pinfunction "SD2/NC_1") (pintype "bidirectional"))
    )
    (net (code "63") (name "unconnected-(U7-CLKOUT-Pad7)") (class "Default")
      (node (ref "U7") (pin "7") (pinfunction "CLKOUT_7") (pintype "output"))
    )
    (net (code "64") (name "~{BOOT}") (class "Default")
      (node (ref "BOOT") (pin "3") (pinfunction "2_3") (pintype "passive"))
      (node (ref "BOOT") (pin "4") (pinfunction "2_4") (pintype "passive"))
      (node (ref "U1") (pin "23") (pinfunction "IO9_23") (pintype "bidirectional"))
    )
    (net (code "65") (name "~{CS}") (class "Default")
      (node (ref "U1") (pin "20") (pinfunction "IO15_20") (pintype "bidirectional"))
      (node (ref "U6") (pin "2") (pinfunction "SD3/~{CS}_2") (pintype "bidirectional"))
    )
    (net (code "66") (name "~{INT_RTC}") (class "Default")
      (node (ref "U1") (pin "13") (pinfunction "IO1_13") (pintype "bidirectional"))
      (node (ref "U7") (pin "3") (pinfunction "~{INT}_3") (pintype "output"))
    )
    (net (code "67") (name "~{RESET}") (class "Default")
      (node (ref "C4") (pin "2") (pinfunction "2_2") (pintype "passive"))
      (node (ref "R2") (pin "1") (pinfunction "1_1") (pintype "passive"))
      (node (ref "RESET") (pin "3") (pinfunction "2_3") (pintype "passive"))
      (node (ref "RESET") (pin "4") (pinfunction "2_4") (pintype "passive"))
    )
    (net (code "68") (name "~{RST_ZMOD4510}") (class "Default")
      (node (ref "IC1") (pin "11") (pinfunction "RES_N_11") (pintype "bidirectional"))
      (node (ref "R9") (pin "1") (pinfunction "1_1") (pintype "passive"))
      (node (ref "U1") (pin "28") (pinfunction "IO22_28") (pintype "bidirectional"))
    )
  )
)
